# galil-router.net
KiCad netlist of a schematic drawn in Altium Designer
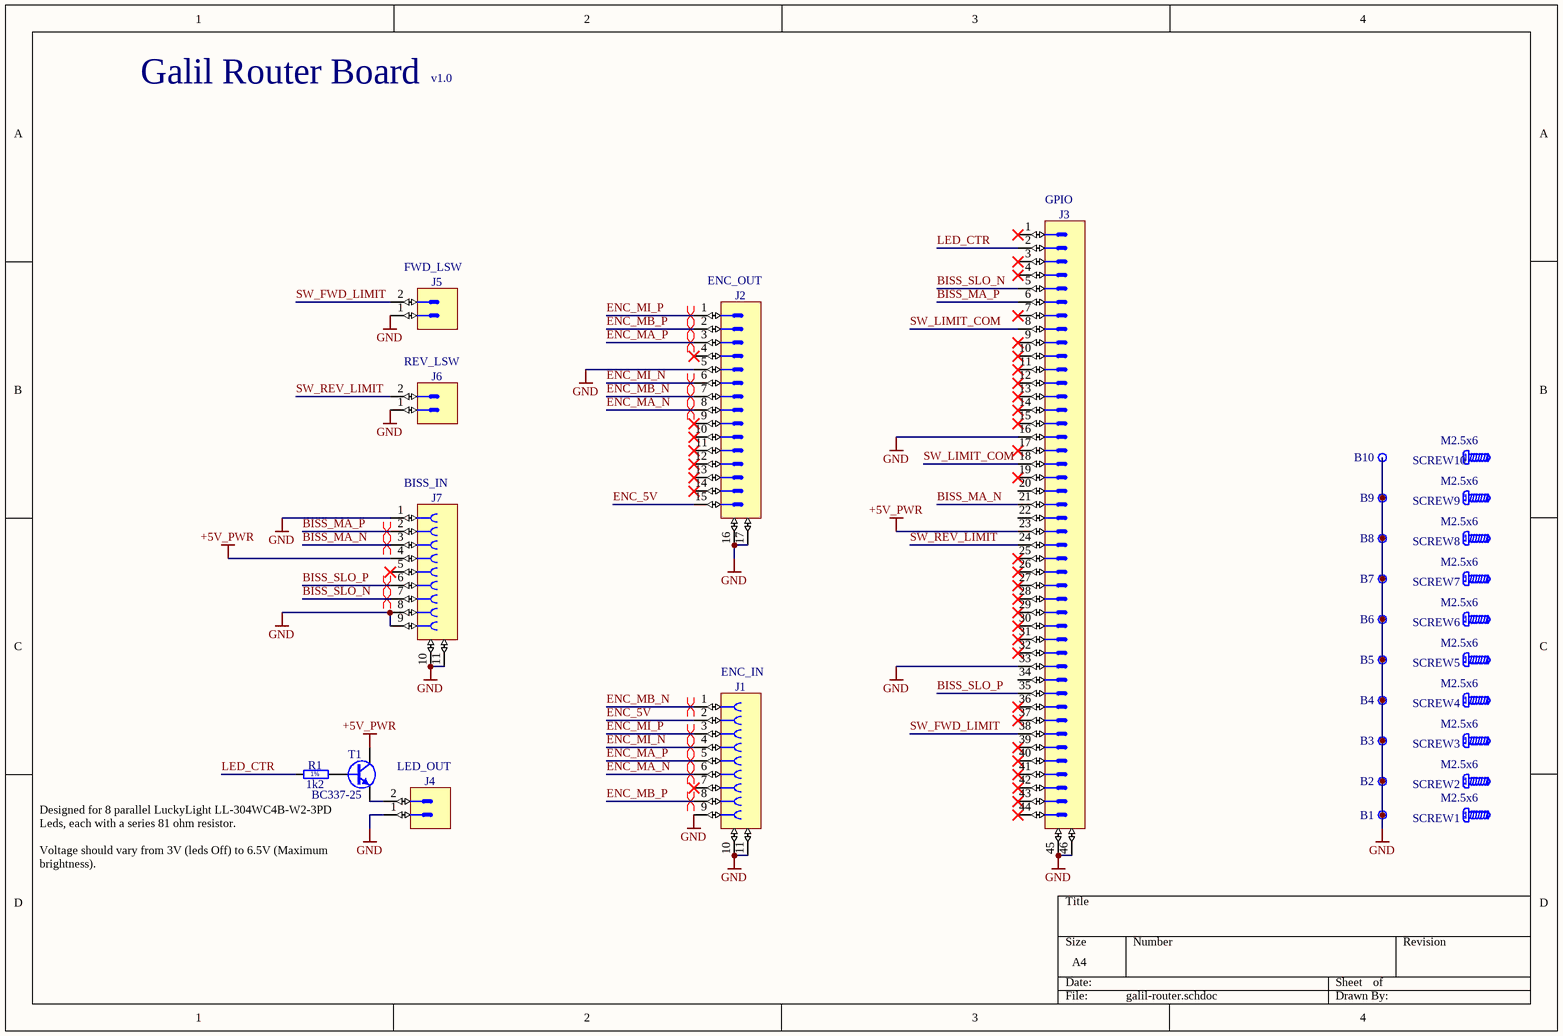
[diagram p0: galil-router.schdoc]

(export (version "E")
  (design (tool "Eeschema 10.0.6"))
  (components
    (comp (ref "B1")
      (value "Plated Hole")
      (footprint "MTG270_500")
      (description "Single Terminal Socket")
      (fields (field (name "PART NUMBER") "PLATED_HOLE2.7_PAD5.0") (field (name "AUTHOR") "CERN DEM JMW"))
      (libsource (lib "Eletro-mechanical") (part "Single Terminal Socket"))
    )
    (comp (ref "B2")
      (value "Plated Hole")
      (footprint "MTG270_500")
      (description "Single Terminal Socket")
      (fields (field (name "PART NUMBER") "PLATED_HOLE2.7_PAD5.0") (field (name "AUTHOR") "CERN DEM JMW"))
      (libsource (lib "Eletro-mechanical") (part "Single Terminal Socket"))
    )
    (comp (ref "B3")
      (value "Plated Hole")
      (footprint "MTG270_500")
      (description "Single Terminal Socket")
      (fields (field (name "PART NUMBER") "PLATED_HOLE2.7_PAD5.0") (field (name "AUTHOR") "CERN DEM JMW"))
      (libsource (lib "Eletro-mechanical") (part "Single Terminal Socket"))
    )
    (comp (ref "B4")
      (value "Plated Hole")
      (footprint "MTG270_500")
      (description "Single Terminal Socket")
      (fields (field (name "PART NUMBER") "PLATED_HOLE2.7_PAD5.0") (field (name "AUTHOR") "CERN DEM JMW"))
      (libsource (lib "Eletro-mechanical") (part "Single Terminal Socket"))
    )
    (comp (ref "B5")
      (value "Plated Hole")
      (footprint "MTG270_500")
      (description "Single Terminal Socket")
      (fields (field (name "PART NUMBER") "PLATED_HOLE2.7_PAD5.0") (field (name "AUTHOR") "CERN DEM JMW"))
      (libsource (lib "Eletro-mechanical") (part "Single Terminal Socket"))
    )
    (comp (ref "B6")
      (value "Plated Hole")
      (footprint "MTG270_500")
      (description "Single Terminal Socket")
      (fields (field (name "PART NUMBER") "PLATED_HOLE2.7_PAD5.0") (field (name "AUTHOR") "CERN DEM JMW"))
      (libsource (lib "Eletro-mechanical") (part "Single Terminal Socket"))
    )
    (comp (ref "B7")
      (value "Plated Hole")
      (footprint "MTG270_500")
      (description "Single Terminal Socket")
      (fields (field (name "PART NUMBER") "PLATED_HOLE2.7_PAD5.0") (field (name "AUTHOR") "CERN DEM JMW"))
      (libsource (lib "Eletro-mechanical") (part "Single Terminal Socket"))
    )
    (comp (ref "B8")
      (value "Plated Hole")
      (footprint "MTG270_500")
      (description "Single Terminal Socket")
      (fields (field (name "PART NUMBER") "PLATED_HOLE2.7_PAD5.0") (field (name "AUTHOR") "CERN DEM JMW"))
      (libsource (lib "Eletro-mechanical") (part "Single Terminal Socket"))
    )
    (comp (ref "B9")
      (value "Plated Hole")
      (footprint "MTG270_500")
      (description "Single Terminal Socket")
      (fields (field (name "PART NUMBER") "PLATED_HOLE2.7_PAD5.0") (field (name "AUTHOR") "CERN DEM JMW"))
      (libsource (lib "Eletro-mechanical") (part "Single Terminal Socket"))
    )
    (comp (ref "B10")
      (value "Plated Hole")
      (footprint "MTG270_500")
      (description "Single Terminal Socket")
      (fields (field (name "PART NUMBER") "PLATED_HOLE2.7_PAD5.0") (field (name "AUTHOR") "CERN DEM JMW"))
      (libsource (lib "Eletro-mechanical") (part "Single Terminal Socket"))
    )
    (comp (ref "J1")
      (value "D-Sub")
      (footprint "AMPHENOL_LD09S24A4GV00LF")
      (description "Connector D-sub 9 Female")
      (fields
        (field (name "PART NUMBER") "AMPHENOL_LD09S24A4GV00LF")
        (field (name "MANUFACTURER") "AMPHENOL")
        (field (name "AUTHOR") "LNLS DIG GBMB")
      )
      (libsource (lib "Connectors_LNLS") (part "Connector D-sub 9 Female"))
    )
    (comp (ref "J2")
      (value "D-Sub")
      (footprint "AMPHENOL_10090928-P154VLF")
      (description "Connector D-sub 15 Male")
      (fields
        (field (name "PART NUMBER") "AMPHENOL_10090928-P154VLF")
        (field (name "MANUFACTURER") "AMPHENOL")
        (field (name "AUTHOR") "LNLS DIG GBMB")
      )
      (libsource (lib "Connectors_LNLS") (part "Connector D-sub 15 Male"))
    )
    (comp (ref "J3")
      (value "D-Sub 44M")
      (footprint "HARTING_09 56 361 5713")
      (description "Connector D-sub 50 Male")
      (fields
        (field (name "PART NUMBER") "HARTING_09 56 361 5713")
        (field (name "MANUFACTURER") "HARTING")
        (field (name "AUTHOR") "LNLS DIG GBMB")
      )
      (libsource (lib "Connectors_LNLS") (part "Connector D-sub 44 Male"))
    )
    (comp (ref "J4")
      (value "Micro-Fit 3.0™")
      (footprint "MOLEX_43650-0228")
      (description "Connector 2 Male")
      (fields
        (field (name "PART NUMBER") "MOLEX_43650-0228")
        (field (name "MANUFACTURER") "MOLEX")
        (field (name "AUTHOR") "LNLS DIG GBMB")
      )
      (libsource (lib "Connectors_LNLS") (part "Connector 2 Male"))
    )
    (comp (ref "J5")
      (value "Micro-Fit 3.0™")
      (footprint "MOLEX_43650-0228")
      (description "Connector 2 Male")
      (fields
        (field (name "PART NUMBER") "MOLEX_43650-0228")
        (field (name "MANUFACTURER") "MOLEX")
        (field (name "AUTHOR") "LNLS DIG GBMB")
      )
      (libsource (lib "Connectors_LNLS") (part "Connector 2 Male"))
    )
    (comp (ref "J6")
      (value "Micro-Fit 3.0™")
      (footprint "MOLEX_43650-0228")
      (description "Connector 2 Male")
      (fields
        (field (name "PART NUMBER") "MOLEX_43650-0228")
        (field (name "MANUFACTURER") "MOLEX")
        (field (name "AUTHOR") "LNLS DIG GBMB")
      )
      (libsource (lib "Connectors_LNLS") (part "Connector 2 Male"))
    )
    (comp (ref "J7")
      (value "D-Sub")
      (footprint "AMPHENOL_LD09S24A4GV00LF")
      (description "Connector D-sub 9 Female")
      (fields
        (field (name "PART NUMBER") "AMPHENOL_LD09S24A4GV00LF")
        (field (name "MANUFACTURER") "AMPHENOL")
        (field (name "AUTHOR") "LNLS DIG GBMB")
      )
      (libsource (lib "Connectors_LNLS") (part "Connector D-sub 9 Female"))
    )
    (comp (ref "R1")
      (value "1k2")
      (footprint "RES1016-630X250")
      (description "Resistor - 1%")
      (fields
        (field (name "PART NUMBER") "RMF_1K2_1%_0.6W_50PPM_1016-630X250")
        (field (name "POWER") "0.6W")
        (field (name "AUTHOR") "CERN DEM JLC")
      )
      (libsource (lib "Resistors") (part "Resistor - 1%"))
    )
    (comp (ref "SCREW1")
      (value "M2.5x6")
      (footprint "BOSSARD_BN5687-3061597_v")
      (description "Screw")
      (fields
        (field (name "PART NUMBER") "BOSSARD_BN5687-3061597_v")
        (field (name "MANUFACTURER") "BOSSARD")
        (field (name "AUTHOR") "CERN DEM JLC")
      )
      (libsource (lib "Eletro-mechanical") (part "Screw"))
    )
    (comp (ref "SCREW2")
      (value "M2.5x6")
      (footprint "BOSSARD_BN5687-3061597_v")
      (description "Screw")
      (fields
        (field (name "PART NUMBER") "BOSSARD_BN5687-3061597_v")
        (field (name "MANUFACTURER") "BOSSARD")
        (field (name "AUTHOR") "CERN DEM JLC")
      )
      (libsource (lib "Eletro-mechanical") (part "Screw"))
    )
    (comp (ref "SCREW3")
      (value "M2.5x6")
      (footprint "BOSSARD_BN5687-3061597_v")
      (description "Screw")
      (fields
        (field (name "PART NUMBER") "BOSSARD_BN5687-3061597_v")
        (field (name "MANUFACTURER") "BOSSARD")
        (field (name "AUTHOR") "CERN DEM JLC")
      )
      (libsource (lib "Eletro-mechanical") (part "Screw"))
    )
    (comp (ref "SCREW4")
      (value "M2.5x6")
      (footprint "BOSSARD_BN5687-3061597_v")
      (description "Screw")
      (fields
        (field (name "PART NUMBER") "BOSSARD_BN5687-3061597_v")
        (field (name "MANUFACTURER") "BOSSARD")
        (field (name "AUTHOR") "CERN DEM JLC")
      )
      (libsource (lib "Eletro-mechanical") (part "Screw"))
    )
    (comp (ref "SCREW5")
      (value "M2.5x6")
      (footprint "BOSSARD_BN5687-3061597_v")
      (description "Screw")
      (fields
        (field (name "PART NUMBER") "BOSSARD_BN5687-3061597_v")
        (field (name "MANUFACTURER") "BOSSARD")
        (field (name "AUTHOR") "CERN DEM JLC")
      )
      (libsource (lib "Eletro-mechanical") (part "Screw"))
    )
    (comp (ref "SCREW6")
      (value "M2.5x6")
      (footprint "BOSSARD_BN5687-3061597_v")
      (description "Screw")
      (fields
        (field (name "PART NUMBER") "BOSSARD_BN5687-3061597_v")
        (field (name "MANUFACTURER") "BOSSARD")
        (field (name "AUTHOR") "CERN DEM JLC")
      )
      (libsource (lib "Eletro-mechanical") (part "Screw"))
    )
    (comp (ref "SCREW7")
      (value "M2.5x6")
      (footprint "BOSSARD_BN5687-3061597_v")
      (description "Screw")
      (fields
        (field (name "PART NUMBER") "BOSSARD_BN5687-3061597_v")
        (field (name "MANUFACTURER") "BOSSARD")
        (field (name "AUTHOR") "CERN DEM JLC")
      )
      (libsource (lib "Eletro-mechanical") (part "Screw"))
    )
    (comp (ref "SCREW8")
      (value "M2.5x6")
      (footprint "BOSSARD_BN5687-3061597_v")
      (description "Screw")
      (fields
        (field (name "PART NUMBER") "BOSSARD_BN5687-3061597_v")
        (field (name "MANUFACTURER") "BOSSARD")
        (field (name "AUTHOR") "CERN DEM JLC")
      )
      (libsource (lib "Eletro-mechanical") (part "Screw"))
    )
    (comp (ref "SCREW9")
      (value "M2.5x6")
      (footprint "BOSSARD_BN5687-3061597_v")
      (description "Screw")
      (fields
        (field (name "PART NUMBER") "BOSSARD_BN5687-3061597_v")
        (field (name "MANUFACTURER") "BOSSARD")
        (field (name "AUTHOR") "CERN DEM JLC")
      )
      (libsource (lib "Eletro-mechanical") (part "Screw"))
    )
    (comp (ref "SCREW10")
      (value "M2.5x6")
      (footprint "BOSSARD_BN5687-3061597_v")
      (description "Screw")
      (fields
        (field (name "PART NUMBER") "BOSSARD_BN5687-3061597_v")
        (field (name "MANUFACTURER") "BOSSARD")
        (field (name "AUTHOR") "CERN DEM JLC")
      )
      (libsource (lib "Eletro-mechanical") (part "Screw"))
    )
    (comp (ref "T1")
      (value "BC337-25")
      (footprint "TO-92AA-P254")
      (description "NPN Transistor")
      (fields (field (name "MANUFACTURER") "NXP SEMICONDUCTORS") (field (name "AUTHOR") "CERN DEM JLC"))
      (libsource (lib "ICs And Semiconductors") (part "NPN C1 B2 E3"))
    )
  )
  (nets
    (net (code "1") (name "+5V_PWR") (class "Default")
      (node (ref "J3") (pin "23") (pinfunction "23_23") (pintype "bidirectional"))
      (node (ref "J7") (pin "4") (pinfunction "4_4") (pintype "bidirectional"))
      (node (ref "T1") (pin "1") (pinfunction "C_1") (pintype "passive"))
    )
    (net (code "2") (name "/BISS_MA_N") (class "Default")
      (node (ref "J3") (pin "21") (pinfunction "21_21") (pintype "bidirectional"))
      (node (ref "J7") (pin "3") (pinfunction "3_3") (pintype "bidirectional"))
    )
    (net (code "3") (name "/BISS_MA_P") (class "Default")
      (node (ref "J3") (pin "6") (pinfunction "6_6") (pintype "bidirectional"))
      (node (ref "J7") (pin "2") (pinfunction "2_2") (pintype "bidirectional"))
    )
    (net (code "4") (name "/BISS_SLO_N") (class "Default")
      (node (ref "J3") (pin "5") (pinfunction "5_5") (pintype "bidirectional"))
      (node (ref "J7") (pin "7") (pinfunction "7_7") (pintype "bidirectional"))
    )
    (net (code "5") (name "/BISS_SLO_P") (class "Default")
      (node (ref "J3") (pin "35") (pinfunction "35_35") (pintype "bidirectional"))
      (node (ref "J7") (pin "6") (pinfunction "6_6") (pintype "bidirectional"))
    )
    (net (code "6") (name "/ENC_5V") (class "Default")
      (node (ref "J1") (pin "2") (pinfunction "2_2") (pintype "bidirectional"))
      (node (ref "J2") (pin "15") (pinfunction "15_15") (pintype "bidirectional"))
    )
    (net (code "7") (name "/ENC_MA_N") (class "Default")
      (node (ref "J1") (pin "6") (pinfunction "6_6") (pintype "bidirectional"))
      (node (ref "J2") (pin "8") (pinfunction "8_8") (pintype "bidirectional"))
    )
    (net (code "8") (name "/ENC_MA_P") (class "Default")
      (node (ref "J1") (pin "5") (pinfunction "5_5") (pintype "bidirectional"))
      (node (ref "J2") (pin "3") (pinfunction "3_3") (pintype "bidirectional"))
    )
    (net (code "9") (name "/ENC_MB_N") (class "Default")
      (node (ref "J1") (pin "1") (pinfunction "1_1") (pintype "bidirectional"))
      (node (ref "J2") (pin "7") (pinfunction "7_7") (pintype "bidirectional"))
    )
    (net (code "10") (name "/ENC_MB_P") (class "Default")
      (node (ref "J1") (pin "8") (pinfunction "8_8") (pintype "bidirectional"))
      (node (ref "J2") (pin "2") (pinfunction "2_2") (pintype "bidirectional"))
    )
    (net (code "11") (name "/ENC_MI_N") (class "Default")
      (node (ref "J1") (pin "4") (pinfunction "4_4") (pintype "bidirectional"))
      (node (ref "J2") (pin "6") (pinfunction "6_6") (pintype "bidirectional"))
    )
    (net (code "12") (name "/ENC_MI_P") (class "Default")
      (node (ref "J1") (pin "3") (pinfunction "3_3") (pintype "bidirectional"))
      (node (ref "J2") (pin "1") (pinfunction "1_1") (pintype "bidirectional"))
    )
    (net (code "13") (name "/LED_CTR") (class "Default")
      (node (ref "J3") (pin "2") (pinfunction "2_2") (pintype "bidirectional"))
      (node (ref "R1") (pin "1") (pinfunction "1_1") (pintype "passive"))
    )
    (net (code "14") (name "/SW_FWD_LIMIT") (class "Default")
      (node (ref "J3") (pin "38") (pinfunction "38_38") (pintype "bidirectional"))
      (node (ref "J5") (pin "2") (pinfunction "2_2") (pintype "bidirectional"))
    )
    (net (code "15") (name "/SW_LIMIT_COM") (class "Default")
      (node (ref "J3") (pin "18") (pinfunction "18_18") (pintype "bidirectional"))
      (node (ref "J3") (pin "8") (pinfunction "8_8") (pintype "bidirectional"))
    )
    (net (code "16") (name "/SW_REV_LIMIT") (class "Default")
      (node (ref "J3") (pin "24") (pinfunction "24_24") (pintype "bidirectional"))
      (node (ref "J6") (pin "2") (pinfunction "2_2") (pintype "bidirectional"))
    )
    (net (code "17") (name "GND") (class "Default")
      (node (ref "B1") (pin "1") (pinfunction "1_1") (pintype "bidirectional"))
      (node (ref "B10") (pin "1") (pinfunction "1_1") (pintype "bidirectional"))
      (node (ref "B2") (pin "1") (pinfunction "1_1") (pintype "bidirectional"))
      (node (ref "B3") (pin "1") (pinfunction "1_1") (pintype "bidirectional"))
      (node (ref "B4") (pin "1") (pinfunction "1_1") (pintype "bidirectional"))
      (node (ref "B5") (pin "1") (pinfunction "1_1") (pintype "bidirectional"))
      (node (ref "B6") (pin "1") (pinfunction "1_1") (pintype "bidirectional"))
      (node (ref "B7") (pin "1") (pinfunction "1_1") (pintype "bidirectional"))
      (node (ref "B8") (pin "1") (pinfunction "1_1") (pintype "bidirectional"))
      (node (ref "B9") (pin "1") (pinfunction "1_1") (pintype "bidirectional"))
      (node (ref "J1") (pin "10") (pinfunction "10_10") (pintype "bidirectional"))
      (node (ref "J1") (pin "11") (pinfunction "11_11") (pintype "bidirectional"))
      (node (ref "J1") (pin "9") (pinfunction "9_9") (pintype "bidirectional"))
      (node (ref "J2") (pin "16") (pinfunction "16_16") (pintype "bidirectional"))
      (node (ref "J2") (pin "17") (pinfunction "17_17") (pintype "bidirectional"))
      (node (ref "J2") (pin "5") (pinfunction "5_5") (pintype "bidirectional"))
      (node (ref "J3") (pin "16") (pinfunction "16_16") (pintype "bidirectional"))
      (node (ref "J3") (pin "33") (pinfunction "33_33") (pintype "bidirectional"))
      (node (ref "J3") (pin "45") (pinfunction "45_45") (pintype "bidirectional"))
      (node (ref "J3") (pin "46") (pinfunction "46_46") (pintype "bidirectional"))
      (node (ref "J4") (pin "1") (pinfunction "1_1") (pintype "bidirectional"))
      (node (ref "J5") (pin "1") (pinfunction "1_1") (pintype "bidirectional"))
      (node (ref "J6") (pin "1") (pinfunction "1_1") (pintype "bidirectional"))
      (node (ref "J7") (pin "1") (pinfunction "1_1") (pintype "bidirectional"))
      (node (ref "J7") (pin "10") (pinfunction "10_10") (pintype "bidirectional"))
      (node (ref "J7") (pin "11") (pinfunction "11_11") (pintype "bidirectional"))
      (node (ref "J7") (pin "8") (pinfunction "8_8") (pintype "bidirectional"))
      (node (ref "J7") (pin "9") (pinfunction "9_9") (pintype "bidirectional"))
    )
    (net (code "18") (name "Net-(T1-B)") (class "Default")
      (node (ref "R1") (pin "2") (pinfunction "2_2") (pintype "passive"))
      (node (ref "T1") (pin "2") (pinfunction "B_2") (pintype "passive"))
    )
    (net (code "19") (name "Net-(T1-E)") (class "Default")
      (node (ref "J4") (pin "2") (pinfunction "2_2") (pintype "bidirectional"))
      (node (ref "T1") (pin "3") (pinfunction "E_3") (pintype "passive"))
    )
    (net (code "20") (name "unconnected-(J1-Pad7)") (class "Default")
      (node (ref "J1") (pin "7") (pinfunction "7_7") (pintype "bidirectional+no_connect"))
    )
    (net (code "21") (name "unconnected-(J2-Pad4)") (class "Default")
      (node (ref "J2") (pin "4") (pinfunction "4_4") (pintype "bidirectional+no_connect"))
    )
    (net (code "22") (name "unconnected-(J2-Pad9)") (class "Default")
      (node (ref "J2") (pin "9") (pinfunction "9_9") (pintype "bidirectional+no_connect"))
    )
    (net (code "23") (name "unconnected-(J2-Pad10)") (class "Default")
      (node (ref "J2") (pin "10") (pinfunction "10_10") (pintype "bidirectional+no_connect"))
    )
    (net (code "24") (name "unconnected-(J2-Pad11)") (class "Default")
      (node (ref "J2") (pin "11") (pinfunction "11_11") (pintype "bidirectional+no_connect"))
    )
    (net (code "25") (name "unconnected-(J2-Pad12)") (class "Default")
      (node (ref "J2") (pin "12") (pinfunction "12_12") (pintype "bidirectional+no_connect"))
    )
    (net (code "26") (name "unconnected-(J2-Pad13)") (class "Default")
      (node (ref "J2") (pin "13") (pinfunction "13_13") (pintype "bidirectional+no_connect"))
    )
    (net (code "27") (name "unconnected-(J2-Pad14)") (class "Default")
      (node (ref "J2") (pin "14") (pinfunction "14_14") (pintype "bidirectional+no_connect"))
    )
    (net (code "28") (name "unconnected-(J3-Pad1)") (class "Default")
      (node (ref "J3") (pin "1") (pinfunction "1_1") (pintype "bidirectional+no_connect"))
    )
    (net (code "29") (name "unconnected-(J3-Pad3)") (class "Default")
      (node (ref "J3") (pin "3") (pinfunction "3_3") (pintype "bidirectional+no_connect"))
    )
    (net (code "30") (name "unconnected-(J3-Pad4)") (class "Default")
      (node (ref "J3") (pin "4") (pinfunction "4_4") (pintype "bidirectional+no_connect"))
    )
    (net (code "31") (name "unconnected-(J3-Pad7)") (class "Default")
      (node (ref "J3") (pin "7") (pinfunction "7_7") (pintype "bidirectional+no_connect"))
    )
    (net (code "32") (name "unconnected-(J3-Pad9)") (class "Default")
      (node (ref "J3") (pin "9") (pinfunction "9_9") (pintype "bidirectional+no_connect"))
    )
    (net (code "33") (name "unconnected-(J3-Pad10)") (class "Default")
      (node (ref "J3") (pin "10") (pinfunction "10_10") (pintype "bidirectional+no_connect"))
    )
    (net (code "34") (name "unconnected-(J3-Pad11)") (class "Default")
      (node (ref "J3") (pin "11") (pinfunction "11_11") (pintype "bidirectional+no_connect"))
    )
    (net (code "35") (name "unconnected-(J3-Pad12)") (class "Default")
      (node (ref "J3") (pin "12") (pinfunction "12_12") (pintype "bidirectional+no_connect"))
    )
    (net (code "36") (name "unconnected-(J3-Pad13)") (class "Default")
      (node (ref "J3") (pin "13") (pinfunction "13_13") (pintype "bidirectional+no_connect"))
    )
    (net (code "37") (name "unconnected-(J3-Pad14)") (class "Default")
      (node (ref "J3") (pin "14") (pinfunction "14_14") (pintype "bidirectional+no_connect"))
    )
    (net (code "38") (name "unconnected-(J3-Pad15)") (class "Default")
      (node (ref "J3") (pin "15") (pinfunction "15_15") (pintype "bidirectional+no_connect"))
    )
    (net (code "39") (name "unconnected-(J3-Pad17)") (class "Default")
      (node (ref "J3") (pin "17") (pinfunction "17_17") (pintype "bidirectional+no_connect"))
    )
    (net (code "40") (name "unconnected-(J3-Pad19)") (class "Default")
      (node (ref "J3") (pin "19") (pinfunction "19_19") (pintype "bidirectional+no_connect"))
    )
    (net (code "41") (name "unconnected-(J3-Pad20)") (class "Default")
      (node (ref "J3") (pin "20") (pinfunction "20_20") (pintype "bidirectional"))
    )
    (net (code "42") (name "unconnected-(J3-Pad22)") (class "Default")
      (node (ref "J3") (pin "22") (pinfunction "22_22") (pintype "bidirectional"))
    )
    (net (code "43") (name "unconnected-(J3-Pad25)") (class "Default")
      (node (ref "J3") (pin "25") (pinfunction "25_25") (pintype "bidirectional+no_connect"))
    )
    (net (code "44") (name "unconnected-(J3-Pad26)") (class "Default")
      (node (ref "J3") (pin "26") (pinfunction "26_26") (pintype "bidirectional+no_connect"))
    )
    (net (code "45") (name "unconnected-(J3-Pad27)") (class "Default")
      (node (ref "J3") (pin "27") (pinfunction "27_27") (pintype "bidirectional+no_connect"))
    )
    (net (code "46") (name "unconnected-(J3-Pad28)") (class "Default")
      (node (ref "J3") (pin "28") (pinfunction "28_28") (pintype "bidirectional+no_connect"))
    )
    (net (code "47") (name "unconnected-(J3-Pad29)") (class "Default")
      (node (ref "J3") (pin "29") (pinfunction "29_29") (pintype "bidirectional+no_connect"))
    )
    (net (code "48") (name "unconnected-(J3-Pad30)") (class "Default")
      (node (ref "J3") (pin "30") (pinfunction "30_30") (pintype "bidirectional+no_connect"))
    )
    (net (code "49") (name "unconnected-(J3-Pad31)") (class "Default")
      (node (ref "J3") (pin "31") (pinfunction "31_31") (pintype "bidirectional+no_connect"))
    )
    (net (code "50") (name "unconnected-(J3-Pad32)") (class "Default")
      (node (ref "J3") (pin "32") (pinfunction "32_32") (pintype "bidirectional+no_connect"))
    )
    (net (code "51") (name "unconnected-(J3-Pad34)") (class "Default")
      (node (ref "J3") (pin "34") (pinfunction "34_34") (pintype "bidirectional"))
    )
    (net (code "52") (name "unconnected-(J3-Pad36)") (class "Default")
      (node (ref "J3") (pin "36") (pinfunction "36_36") (pintype "bidirectional+no_connect"))
    )
    (net (code "53") (name "unconnected-(J3-Pad37)") (class "Default")
      (node (ref "J3") (pin "37") (pinfunction "37_37") (pintype "bidirectional+no_connect"))
    )
    (net (code "54") (name "unconnected-(J3-Pad39)") (class "Default")
      (node (ref "J3") (pin "39") (pinfunction "39_39") (pintype "bidirectional+no_connect"))
    )
    (net (code "55") (name "unconnected-(J3-Pad40)") (class "Default")
      (node (ref "J3") (pin "40") (pinfunction "40_40") (pintype "bidirectional+no_connect"))
    )
    (net (code "56") (name "unconnected-(J3-Pad41)") (class "Default")
      (node (ref "J3") (pin "41") (pinfunction "41_41") (pintype "bidirectional+no_connect"))
    )
    (net (code "57") (name "unconnected-(J3-Pad42)") (class "Default")
      (node (ref "J3") (pin "42") (pinfunction "42_42") (pintype "bidirectional+no_connect"))
    )
    (net (code "58") (name "unconnected-(J3-Pad43)") (class "Default")
      (node (ref "J3") (pin "43") (pinfunction "43_43") (pintype "bidirectional+no_connect"))
    )
    (net (code "59") (name "unconnected-(J3-Pad44)") (class "Default")
      (node (ref "J3") (pin "44") (pinfunction "44_44") (pintype "bidirectional+no_connect"))
    )
    (net (code "60") (name "unconnected-(J7-Pad5)") (class "Default")
      (node (ref "J7") (pin "5") (pinfunction "5_5") (pintype "bidirectional+no_connect"))
    )
  )
)
